# YuSynth_VCA_Eurorack_v1.net
KiCad netlist of a schematic drawn in EAGLE
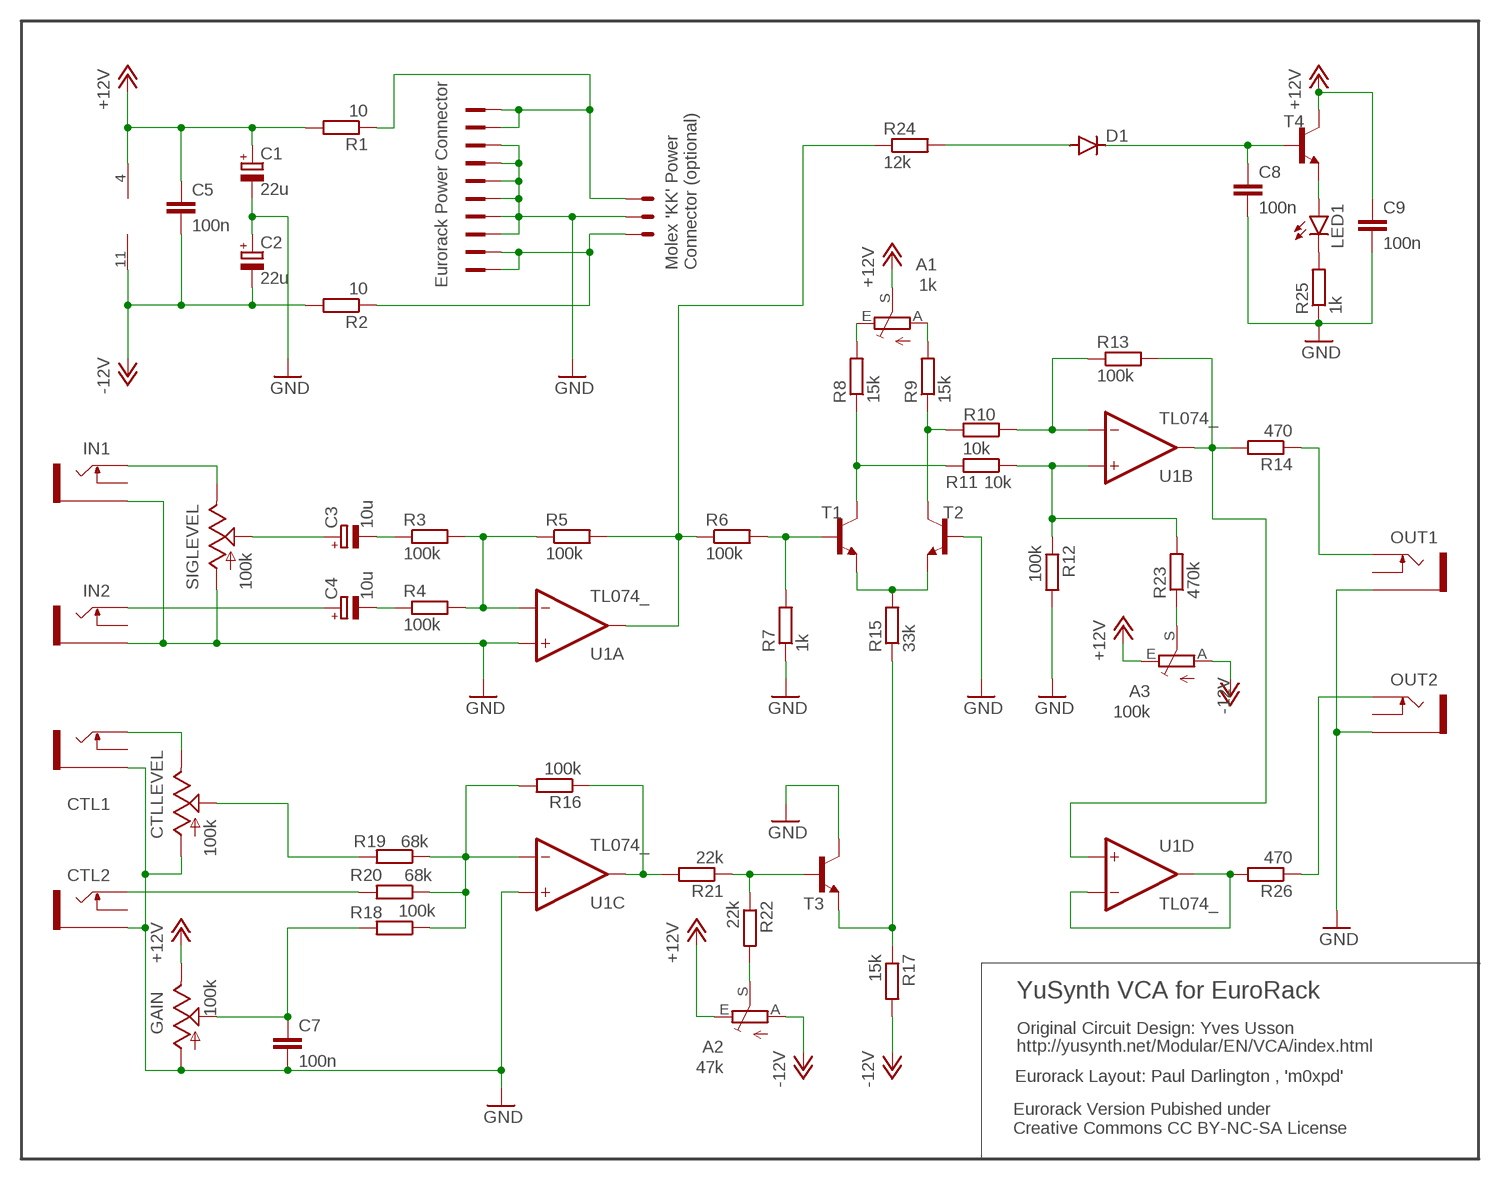
[diagram p0: schematic, sheet 1]

(export (version "E")
  (design (tool "Eeschema 10.0.6"))
  (components
    (comp (ref "A1")
      (value "1k")
      (footprint "eagle-import:B25P")
      (libsource (lib "eagle-import") (part "TRIM_EU-B25P"))
    )
    (comp (ref "A2")
      (value "47k")
      (footprint "eagle-import:B25P")
      (libsource (lib "eagle-import") (part "TRIM_EU-B25P"))
    )
    (comp (ref "A3")
      (value "100k")
      (footprint "eagle-import:B25P")
      (libsource (lib "eagle-import") (part "TRIM_EU-B25P"))
    )
    (comp (ref "C1")
      (value "22u")
      (footprint "eagle-import:E2,5-5")
      (libsource (lib "eagle-import") (part "CPOL-EUE2.5-5"))
    )
    (comp (ref "C2")
      (value "22u")
      (footprint "eagle-import:E2,5-5")
      (libsource (lib "eagle-import") (part "CPOL-EUE2.5-5"))
    )
    (comp (ref "C3")
      (value "10u")
      (footprint "eagle-import:E2,5-5")
      (libsource (lib "eagle-import") (part "CPOL-EUE2.5-5"))
    )
    (comp (ref "C4")
      (value "10u")
      (footprint "eagle-import:E2,5-5")
      (libsource (lib "eagle-import") (part "CPOL-EUE2.5-5"))
    )
    (comp (ref "C5")
      (value "100n")
      (footprint "eagle-import:C050-025X075")
      (libsource (lib "eagle-import") (part "C-EU050-025X075"))
    )
    (comp (ref "C7")
      (value "100n")
      (footprint "eagle-import:C050-025X075")
      (libsource (lib "eagle-import") (part "C-EU050-025X075"))
    )
    (comp (ref "C8")
      (value "100n")
      (footprint "eagle-import:C050-025X075")
      (libsource (lib "eagle-import") (part "C-EU050-025X075"))
    )
    (comp (ref "C9")
      (value "100n")
      (footprint "eagle-import:C050-025X075")
      (libsource (lib "eagle-import") (part "C-EU050-025X075"))
    )
    (comp (ref "CTL1")
      (value "THONKICONNNEW")
      (footprint "eagle-import:WQP-PJ301M-12_JACK")
      (libsource (lib "eagle-import") (part "THONKICONNNEW"))
    )
    (comp (ref "CTL2")
      (value "THONKICONNNEW")
      (footprint "eagle-import:WQP-PJ301M-12_JACK")
      (libsource (lib "eagle-import") (part "THONKICONNNEW"))
    )
    (comp (ref "CTLLEVEL")
      (value "100k")
      (footprint "eagle-import:9MM_SNAP-IN_POT")
      (libsource (lib "eagle-import") (part "9MM_SNAP-IN_POT_"))
    )
    (comp (ref "D1")
      (value "1N4148DO35-7")
      (footprint "eagle-import:DO35-7")
      (libsource (lib "eagle-import") (part "1N4148DO35-7"))
    )
    (comp (ref "EURORACK_POWER")
      (value "2510-")
      (footprint "eagle-import:PAK100_2500-10")
      (fields (field (name "MF") "3M") (field (name "MPN") "2510-6002UB"))
      (libsource (lib "eagle-import") (part "2510-"))
    )
    (comp (ref "GAIN")
      (value "100k")
      (footprint "eagle-import:9MM_SNAP-IN_POT")
      (libsource (lib "eagle-import") (part "9MM_SNAP-IN_POT_"))
    )
    (comp (ref "IN1")
      (value "THONKICONNNEW")
      (footprint "eagle-import:WQP-PJ301M-12_JACK")
      (libsource (lib "eagle-import") (part "THONKICONNNEW"))
    )
    (comp (ref "IN2")
      (value "THONKICONNNEW")
      (footprint "eagle-import:WQP-PJ301M-12_JACK")
      (libsource (lib "eagle-import") (part "THONKICONNNEW"))
    )
    (comp (ref "LED1")
      (value "LED3MM")
      (footprint "eagle-import:LED3MM")
      (libsource (lib "eagle-import") (part "LED3MM"))
    )
    (comp (ref "OUT1")
      (value "THONKICONNNEW")
      (footprint "eagle-import:WQP-PJ301M-12_JACK")
      (libsource (lib "eagle-import") (part "THONKICONNNEW"))
    )
    (comp (ref "OUT2")
      (value "THONKICONNNEW")
      (footprint "eagle-import:WQP-PJ301M-12_JACK")
      (libsource (lib "eagle-import") (part "THONKICONNNEW"))
    )
    (comp (ref "POWER")
      (value "22-23-2031")
      (footprint "eagle-import:22-23-2031")
      (fields (field (name "MF") "MOLEX"))
      (libsource (lib "eagle-import") (part "22-23-2031"))
    )
    (comp (ref "R1")
      (value "10")
      (footprint "eagle-import:0204_7")
      (libsource (lib "eagle-import") (part "R-EU_0204/7"))
    )
    (comp (ref "R2")
      (value "10")
      (footprint "eagle-import:0204_7")
      (libsource (lib "eagle-import") (part "R-EU_0204/7"))
    )
    (comp (ref "R3")
      (value "100k")
      (footprint "eagle-import:0204_7")
      (libsource (lib "eagle-import") (part "R-EU_0204/7"))
    )
    (comp (ref "R4")
      (value "100k")
      (footprint "eagle-import:0204_7")
      (libsource (lib "eagle-import") (part "R-EU_0204/7"))
    )
    (comp (ref "R5")
      (value "100k")
      (footprint "eagle-import:0204_7")
      (libsource (lib "eagle-import") (part "R-EU_0204/7"))
    )
    (comp (ref "R6")
      (value "100k")
      (footprint "eagle-import:0204_7")
      (libsource (lib "eagle-import") (part "R-EU_0204/7"))
    )
    (comp (ref "R7")
      (value "1k")
      (footprint "eagle-import:0204_7")
      (libsource (lib "eagle-import") (part "R-EU_0204/7"))
    )
    (comp (ref "R8")
      (value "15k")
      (footprint "eagle-import:0204_7")
      (libsource (lib "eagle-import") (part "R-EU_0204/7"))
    )
    (comp (ref "R9")
      (value "15k")
      (footprint "eagle-import:0204_7")
      (libsource (lib "eagle-import") (part "R-EU_0204/7"))
    )
    (comp (ref "R10")
      (value "10k")
      (footprint "eagle-import:0204_7")
      (libsource (lib "eagle-import") (part "R-EU_0204/7"))
    )
    (comp (ref "R11")
      (value "10k")
      (footprint "eagle-import:0204_7")
      (libsource (lib "eagle-import") (part "R-EU_0204/7"))
    )
    (comp (ref "R12")
      (value "100k")
      (footprint "eagle-import:0204_7")
      (libsource (lib "eagle-import") (part "R-EU_0204/7"))
    )
    (comp (ref "R13")
      (value "100k")
      (footprint "eagle-import:0204_7")
      (libsource (lib "eagle-import") (part "R-EU_0204/7"))
    )
    (comp (ref "R14")
      (value "470")
      (footprint "eagle-import:0204_7")
      (libsource (lib "eagle-import") (part "R-EU_0204/7"))
    )
    (comp (ref "R15")
      (value "33k")
      (footprint "eagle-import:0204_7")
      (libsource (lib "eagle-import") (part "R-EU_0204/7"))
    )
    (comp (ref "R16")
      (value "100k")
      (footprint "eagle-import:0204_7")
      (libsource (lib "eagle-import") (part "R-EU_0204/7"))
    )
    (comp (ref "R17")
      (value "15k")
      (footprint "eagle-import:0204_7")
      (libsource (lib "eagle-import") (part "R-EU_0204/7"))
    )
    (comp (ref "R18")
      (value "100k")
      (footprint "eagle-import:0204_7")
      (libsource (lib "eagle-import") (part "R-EU_0204/7"))
    )
    (comp (ref "R19")
      (value "68k")
      (footprint "eagle-import:0204_7")
      (libsource (lib "eagle-import") (part "R-EU_0204/7"))
    )
    (comp (ref "R20")
      (value "68k")
      (footprint "eagle-import:0204_7")
      (libsource (lib "eagle-import") (part "R-EU_0204/7"))
    )
    (comp (ref "R21")
      (value "22k")
      (footprint "eagle-import:0204_7")
      (libsource (lib "eagle-import") (part "R-EU_0204/7"))
    )
    (comp (ref "R22")
      (value "22k")
      (footprint "eagle-import:0204_7")
      (libsource (lib "eagle-import") (part "R-EU_0204/7"))
    )
    (comp (ref "R23")
      (value "470k")
      (footprint "eagle-import:0204_7")
      (libsource (lib "eagle-import") (part "R-EU_0204/7"))
    )
    (comp (ref "R24")
      (value "12k")
      (footprint "eagle-import:0204_7")
      (libsource (lib "eagle-import") (part "R-EU_0204/7"))
    )
    (comp (ref "R25")
      (value "1k")
      (footprint "eagle-import:0204_7")
      (libsource (lib "eagle-import") (part "R-EU_0204/7"))
    )
    (comp (ref "R26")
      (value "470")
      (footprint "eagle-import:0204_7")
      (libsource (lib "eagle-import") (part "R-EU_0204/7"))
    )
    (comp (ref "SIGLEVEL")
      (value "100k")
      (footprint "eagle-import:9MM_SNAP-IN_POT")
      (libsource (lib "eagle-import") (part "9MM_SNAP-IN_POT_"))
    )
    (comp (ref "T1")
      (value "2N3904")
      (footprint "eagle-import:TO92")
      (libsource (lib "eagle-import") (part "2N3904"))
    )
    (comp (ref "T2")
      (value "2N3904")
      (footprint "eagle-import:TO92")
      (libsource (lib "eagle-import") (part "2N3904"))
    )
    (comp (ref "T3")
      (value "2N3904")
      (footprint "eagle-import:TO92")
      (libsource (lib "eagle-import") (part "2N3904"))
    )
    (comp (ref "T4")
      (value "2N3904")
      (footprint "eagle-import:TO92")
      (libsource (lib "eagle-import") (part "2N3904"))
    )
    (comp (ref "U1")
      (value "TL074_")
      (footprint "eagle-import:DIL14")
      (libsource (lib "eagle-import") (part "TL074_"))
    )
  )
  (nets
    (net (code "1") (name "+12V") (class "Default")
      (node (ref "A1") (pin "S") (pinfunction "S_S") (pintype "passive"))
      (node (ref "A2") (pin "E") (pinfunction "E_E") (pintype "passive"))
      (node (ref "A3") (pin "E") (pinfunction "E_E") (pintype "passive"))
      (node (ref "C1") (pin "+") (pinfunction "+_+") (pintype "passive"))
      (node (ref "C5") (pin "1") (pinfunction "1_1") (pintype "passive"))
      (node (ref "C9") (pin "1") (pinfunction "1_1") (pintype "passive"))
      (node (ref "GAIN") (pin "3") (pinfunction "E_3") (pintype "passive"))
      (node (ref "R1") (pin "2") (pinfunction "2_2") (pintype "passive"))
      (node (ref "T4") (pin "1") (pinfunction "C_1") (pintype "passive"))
      (node (ref "U1") (pin "4") (pinfunction "V+_4") (pintype "power_in"))
    )
    (net (code "2") (name "-12V") (class "Default")
      (node (ref "A2") (pin "A") (pinfunction "A_A") (pintype "passive"))
      (node (ref "A3") (pin "A") (pinfunction "A_A") (pintype "passive"))
      (node (ref "C2") (pin "-") (pinfunction "-_-") (pintype "passive"))
      (node (ref "C5") (pin "2") (pinfunction "2_2") (pintype "passive"))
      (node (ref "R17") (pin "2") (pinfunction "2_2") (pintype "passive"))
      (node (ref "R2") (pin "2") (pinfunction "2_2") (pintype "passive"))
      (node (ref "U1") (pin "11") (pinfunction "V-_11") (pintype "power_in"))
    )
    (net (code "3") (name "GND") (class "Default")
      (node (ref "C1") (pin "-") (pinfunction "-_-") (pintype "passive"))
      (node (ref "C2") (pin "+") (pinfunction "+_+") (pintype "passive"))
      (node (ref "C7") (pin "2") (pinfunction "2_2") (pintype "passive"))
      (node (ref "C8") (pin "2") (pinfunction "2_2") (pintype "passive"))
      (node (ref "C9") (pin "2") (pinfunction "2_2") (pintype "passive"))
      (node (ref "CTL1") (pin "P$3_SLEEVE") (pinfunction "SLEEVE_P$3_SLEEVE") (pintype "passive"))
      (node (ref "CTL2") (pin "P$3_SLEEVE") (pinfunction "SLEEVE_P$3_SLEEVE") (pintype "passive"))
      (node (ref "CTLLEVEL") (pin "1") (pinfunction "A_1") (pintype "passive"))
      (node (ref "EURORACK_POWER") (pin "3") (pinfunction "KL_3") (pintype "passive"))
      (node (ref "EURORACK_POWER") (pin "4") (pinfunction "KL_4") (pintype "passive"))
      (node (ref "EURORACK_POWER") (pin "5") (pinfunction "KL_5") (pintype "passive"))
      (node (ref "EURORACK_POWER") (pin "6") (pinfunction "KL_6") (pintype "passive"))
      (node (ref "EURORACK_POWER") (pin "7") (pinfunction "KL_7") (pintype "passive"))
      (node (ref "EURORACK_POWER") (pin "8") (pinfunction "KL_8") (pintype "passive"))
      (node (ref "GAIN") (pin "1") (pinfunction "A_1") (pintype "passive"))
      (node (ref "IN1") (pin "P$3_SLEEVE") (pinfunction "SLEEVE_P$3_SLEEVE") (pintype "passive"))
      (node (ref "IN2") (pin "P$3_SLEEVE") (pinfunction "SLEEVE_P$3_SLEEVE") (pintype "passive"))
      (node (ref "OUT1") (pin "P$3_SLEEVE") (pinfunction "SLEEVE_P$3_SLEEVE") (pintype "passive"))
      (node (ref "OUT2") (pin "P$3_SLEEVE") (pinfunction "SLEEVE_P$3_SLEEVE") (pintype "passive"))
      (node (ref "POWER") (pin "2") (pinfunction "S_2") (pintype "passive"))
      (node (ref "R12") (pin "2") (pinfunction "2_2") (pintype "passive"))
      (node (ref "R25") (pin "1") (pinfunction "1_1") (pintype "passive"))
      (node (ref "R7") (pin "1") (pinfunction "1_1") (pintype "passive"))
      (node (ref "SIGLEVEL") (pin "1") (pinfunction "A_1") (pintype "passive"))
      (node (ref "T2") (pin "2") (pinfunction "B_2") (pintype "passive"))
      (node (ref "T3") (pin "1") (pinfunction "C_1") (pintype "passive"))
      (node (ref "U1") (pin "10") (pinfunction "+IN_10") (pintype "input"))
      (node (ref "U1") (pin "3") (pinfunction "+IN_3") (pintype "input"))
    )
    (net (code "4") (name "Net-(A1-PadA)") (class "Default")
      (node (ref "A1") (pin "A") (pinfunction "A_A") (pintype "passive"))
      (node (ref "R9") (pin "2") (pinfunction "2_2") (pintype "passive"))
    )
    (net (code "5") (name "Net-(A1-PadE)") (class "Default")
      (node (ref "A1") (pin "E") (pinfunction "E_E") (pintype "passive"))
      (node (ref "R8") (pin "2") (pinfunction "2_2") (pintype "passive"))
    )
    (net (code "6") (name "Net-(A2-PadS)") (class "Default")
      (node (ref "A2") (pin "S") (pinfunction "S_S") (pintype "passive"))
      (node (ref "R22") (pin "2") (pinfunction "2_2") (pintype "passive"))
    )
    (net (code "7") (name "Net-(A3-PadS)") (class "Default")
      (node (ref "A3") (pin "S") (pinfunction "S_S") (pintype "passive"))
      (node (ref "R23") (pin "1") (pinfunction "1_1") (pintype "passive"))
    )
    (net (code "8") (name "Net-(C3-Pad-)") (class "Default")
      (node (ref "C3") (pin "-") (pinfunction "-_-") (pintype "passive"))
      (node (ref "R3") (pin "1") (pinfunction "1_1") (pintype "passive"))
    )
    (net (code "9") (name "Net-(C4-Pad-)") (class "Default")
      (node (ref "C4") (pin "-") (pinfunction "-_-") (pintype "passive"))
      (node (ref "R4") (pin "1") (pinfunction "1_1") (pintype "passive"))
    )
    (net (code "10") (name "Net-(CTL1-TIP)") (class "Default")
      (node (ref "CTL1") (pin "P$1_TIP") (pinfunction "TIP_P$1_TIP") (pintype "passive"))
      (node (ref "CTLLEVEL") (pin "3") (pinfunction "E_3") (pintype "passive"))
    )
    (net (code "11") (name "Net-(CTL2-TIP)") (class "Default")
      (node (ref "CTL2") (pin "P$1_TIP") (pinfunction "TIP_P$1_TIP") (pintype "passive"))
      (node (ref "R20") (pin "2") (pinfunction "2_2") (pintype "passive"))
    )
    (net (code "12") (name "Net-(CTLLEVEL-S)") (class "Default")
      (node (ref "CTLLEVEL") (pin "2") (pinfunction "S_2") (pintype "passive"))
      (node (ref "R19") (pin "2") (pinfunction "2_2") (pintype "passive"))
    )
    (net (code "13") (name "Net-(D1-PadA)") (class "Default")
      (node (ref "D1") (pin "A") (pinfunction "A_A") (pintype "passive"))
      (node (ref "R24") (pin "2") (pinfunction "2_2") (pintype "passive"))
    )
    (net (code "14") (name "Net-(EURORACK_POWERA-KL)") (class "Default")
      (node (ref "EURORACK_POWER") (pin "1") (pinfunction "KL_1") (pintype "passive"))
      (node (ref "EURORACK_POWER") (pin "2") (pinfunction "KL_2") (pintype "passive"))
      (node (ref "POWER") (pin "3") (pinfunction "S_3") (pintype "passive"))
      (node (ref "R2") (pin "1") (pinfunction "1_1") (pintype "passive"))
    )
    (net (code "15") (name "Net-(EURORACK_POWERB-KL)") (class "Default")
      (node (ref "EURORACK_POWER") (pin "10") (pinfunction "KL_10") (pintype "passive"))
      (node (ref "EURORACK_POWER") (pin "9") (pinfunction "KL_9") (pintype "passive"))
      (node (ref "POWER") (pin "1") (pinfunction "S_1") (pintype "passive"))
      (node (ref "R1") (pin "1") (pinfunction "1_1") (pintype "passive"))
    )
    (net (code "16") (name "Net-(GAIN-S)") (class "Default")
      (node (ref "C7") (pin "1") (pinfunction "1_1") (pintype "passive"))
      (node (ref "GAIN") (pin "2") (pinfunction "S_2") (pintype "passive"))
      (node (ref "R18") (pin "2") (pinfunction "2_2") (pintype "passive"))
    )
    (net (code "17") (name "Net-(IN1-TIP)") (class "Default")
      (node (ref "IN1") (pin "P$1_TIP") (pinfunction "TIP_P$1_TIP") (pintype "passive"))
      (node (ref "SIGLEVEL") (pin "3") (pinfunction "E_3") (pintype "passive"))
    )
    (net (code "18") (name "Net-(IN2-TIP)") (class "Default")
      (node (ref "C4") (pin "+") (pinfunction "+_+") (pintype "passive"))
      (node (ref "IN2") (pin "P$1_TIP") (pinfunction "TIP_P$1_TIP") (pintype "passive"))
    )
    (net (code "19") (name "Net-(LED1-C)") (class "Default")
      (node (ref "LED1") (pin "K") (pinfunction "C_K") (pintype "passive"))
      (node (ref "R25") (pin "2") (pinfunction "2_2") (pintype "passive"))
    )
    (net (code "20") (name "Net-(OUT1-TIP)") (class "Default")
      (node (ref "OUT1") (pin "P$1_TIP") (pinfunction "TIP_P$1_TIP") (pintype "passive"))
      (node (ref "R14") (pin "1") (pinfunction "1_1") (pintype "passive"))
    )
    (net (code "21") (name "Net-(OUT2-TIP)") (class "Default")
      (node (ref "OUT2") (pin "P$1_TIP") (pinfunction "TIP_P$1_TIP") (pintype "passive"))
      (node (ref "R26") (pin "1") (pinfunction "1_1") (pintype "passive"))
    )
    (net (code "22") (name "Net-(SIGLEVEL-S)") (class "Default")
      (node (ref "C3") (pin "+") (pinfunction "+_+") (pintype "passive"))
      (node (ref "SIGLEVEL") (pin "2") (pinfunction "S_2") (pintype "passive"))
    )
    (net (code "23") (name "Net-(T1-B)") (class "Default")
      (node (ref "R6") (pin "2") (pinfunction "2_2") (pintype "passive"))
      (node (ref "R7") (pin "2") (pinfunction "2_2") (pintype "passive"))
      (node (ref "T1") (pin "2") (pinfunction "B_2") (pintype "passive"))
    )
    (net (code "24") (name "Net-(T1-C)") (class "Default")
      (node (ref "R11") (pin "2") (pinfunction "2_2") (pintype "passive"))
      (node (ref "R8") (pin "1") (pinfunction "1_1") (pintype "passive"))
      (node (ref "T1") (pin "1") (pinfunction "C_1") (pintype "passive"))
    )
    (net (code "25") (name "Net-(T1-E)") (class "Default")
      (node (ref "R15") (pin "2") (pinfunction "2_2") (pintype "passive"))
      (node (ref "T1") (pin "3") (pinfunction "E_3") (pintype "passive"))
      (node (ref "T2") (pin "3") (pinfunction "E_3") (pintype "passive"))
    )
    (net (code "26") (name "Net-(T2-C)") (class "Default")
      (node (ref "R10") (pin "2") (pinfunction "2_2") (pintype "passive"))
      (node (ref "R9") (pin "1") (pinfunction "1_1") (pintype "passive"))
      (node (ref "T2") (pin "1") (pinfunction "C_1") (pintype "passive"))
    )
    (net (code "27") (name "Net-(T3-B)") (class "Default")
      (node (ref "R21") (pin "1") (pinfunction "1_1") (pintype "passive"))
      (node (ref "R22") (pin "1") (pinfunction "1_1") (pintype "passive"))
      (node (ref "T3") (pin "2") (pinfunction "B_2") (pintype "passive"))
    )
    (net (code "28") (name "Net-(T3-E)") (class "Default")
      (node (ref "R15") (pin "1") (pinfunction "1_1") (pintype "passive"))
      (node (ref "R17") (pin "1") (pinfunction "1_1") (pintype "passive"))
      (node (ref "T3") (pin "3") (pinfunction "E_3") (pintype "passive"))
    )
    (net (code "29") (name "Net-(T4-B)") (class "Default")
      (node (ref "C8") (pin "1") (pinfunction "1_1") (pintype "passive"))
      (node (ref "D1") (pin "C") (pinfunction "C_C") (pintype "passive"))
      (node (ref "T4") (pin "2") (pinfunction "B_2") (pintype "passive"))
    )
    (net (code "30") (name "Net-(T4-E)") (class "Default")
      (node (ref "LED1") (pin "A") (pinfunction "A_A") (pintype "passive"))
      (node (ref "T4") (pin "3") (pinfunction "E_3") (pintype "passive"))
    )
    (net (code "31") (name "Net-(U1A--IN)") (class "Default")
      (node (ref "R3") (pin "2") (pinfunction "2_2") (pintype "passive"))
      (node (ref "R4") (pin "2") (pinfunction "2_2") (pintype "passive"))
      (node (ref "R5") (pin "1") (pinfunction "1_1") (pintype "passive"))
      (node (ref "U1") (pin "2") (pinfunction "-IN_2") (pintype "input"))
    )
    (net (code "32") (name "Net-(U1A-OUT)") (class "Default")
      (node (ref "R24") (pin "1") (pinfunction "1_1") (pintype "passive"))
      (node (ref "R5") (pin "2") (pinfunction "2_2") (pintype "passive"))
      (node (ref "R6") (pin "1") (pinfunction "1_1") (pintype "passive"))
      (node (ref "U1") (pin "1") (pinfunction "OUT_1") (pintype "output"))
    )
    (net (code "33") (name "Net-(U1B-+IN)") (class "Default")
      (node (ref "R11") (pin "1") (pinfunction "1_1") (pintype "passive"))
      (node (ref "R12") (pin "1") (pinfunction "1_1") (pintype "passive"))
      (node (ref "R23") (pin "2") (pinfunction "2_2") (pintype "passive"))
      (node (ref "U1") (pin "5") (pinfunction "+IN_5") (pintype "input"))
    )
    (net (code "34") (name "Net-(U1B--IN)") (class "Default")
      (node (ref "R10") (pin "1") (pinfunction "1_1") (pintype "passive"))
      (node (ref "R13") (pin "1") (pinfunction "1_1") (pintype "passive"))
      (node (ref "U1") (pin "6") (pinfunction "-IN_6") (pintype "input"))
    )
    (net (code "35") (name "Net-(U1B-OUT)") (class "Default")
      (node (ref "R13") (pin "2") (pinfunction "2_2") (pintype "passive"))
      (node (ref "R14") (pin "2") (pinfunction "2_2") (pintype "passive"))
      (node (ref "U1") (pin "12") (pinfunction "+IN_12") (pintype "input"))
      (node (ref "U1") (pin "7") (pinfunction "OUT_7") (pintype "output"))
    )
    (net (code "36") (name "Net-(U1C--IN)") (class "Default")
      (node (ref "R16") (pin "2") (pinfunction "2_2") (pintype "passive"))
      (node (ref "R18") (pin "1") (pinfunction "1_1") (pintype "passive"))
      (node (ref "R19") (pin "1") (pinfunction "1_1") (pintype "passive"))
      (node (ref "R20") (pin "1") (pinfunction "1_1") (pintype "passive"))
      (node (ref "U1") (pin "9") (pinfunction "-IN_9") (pintype "input"))
    )
    (net (code "37") (name "Net-(U1C-OUT)") (class "Default")
      (node (ref "R16") (pin "1") (pinfunction "1_1") (pintype "passive"))
      (node (ref "R21") (pin "2") (pinfunction "2_2") (pintype "passive"))
      (node (ref "U1") (pin "8") (pinfunction "OUT_8") (pintype "output"))
    )
    (net (code "38") (name "Net-(U1D--IN)") (class "Default")
      (node (ref "R26") (pin "2") (pinfunction "2_2") (pintype "passive"))
      (node (ref "U1") (pin "13") (pinfunction "-IN_13") (pintype "input"))
      (node (ref "U1") (pin "14") (pinfunction "OUT_14") (pintype "output"))
    )
    (net (code "39") (name "unconnected-(CTL1-SWITCH-PadP$2_SWITCH)") (class "Default")
      (node (ref "CTL1") (pin "P$2_SWITCH") (pinfunction "SWITCH_P$2_SWITCH") (pintype "passive"))
    )
    (net (code "40") (name "unconnected-(CTL2-SWITCH-PadP$2_SWITCH)") (class "Default")
      (node (ref "CTL2") (pin "P$2_SWITCH") (pinfunction "SWITCH_P$2_SWITCH") (pintype "passive"))
    )
    (net (code "41") (name "unconnected-(IN1-SWITCH-PadP$2_SWITCH)") (class "Default")
      (node (ref "IN1") (pin "P$2_SWITCH") (pinfunction "SWITCH_P$2_SWITCH") (pintype "passive"))
    )
    (net (code "42") (name "unconnected-(IN2-SWITCH-PadP$2_SWITCH)") (class "Default")
      (node (ref "IN2") (pin "P$2_SWITCH") (pinfunction "SWITCH_P$2_SWITCH") (pintype "passive"))
    )
    (net (code "43") (name "unconnected-(OUT1-SWITCH-PadP$2_SWITCH)") (class "Default")
      (node (ref "OUT1") (pin "P$2_SWITCH") (pinfunction "SWITCH_P$2_SWITCH") (pintype "passive"))
    )
    (net (code "44") (name "unconnected-(OUT2-SWITCH-PadP$2_SWITCH)") (class "Default")
      (node (ref "OUT2") (pin "P$2_SWITCH") (pinfunction "SWITCH_P$2_SWITCH") (pintype "passive"))
    )
  )
)
